# CL-400-5-R4.net
KiCad netlist of a schematic drawn in EAGLE
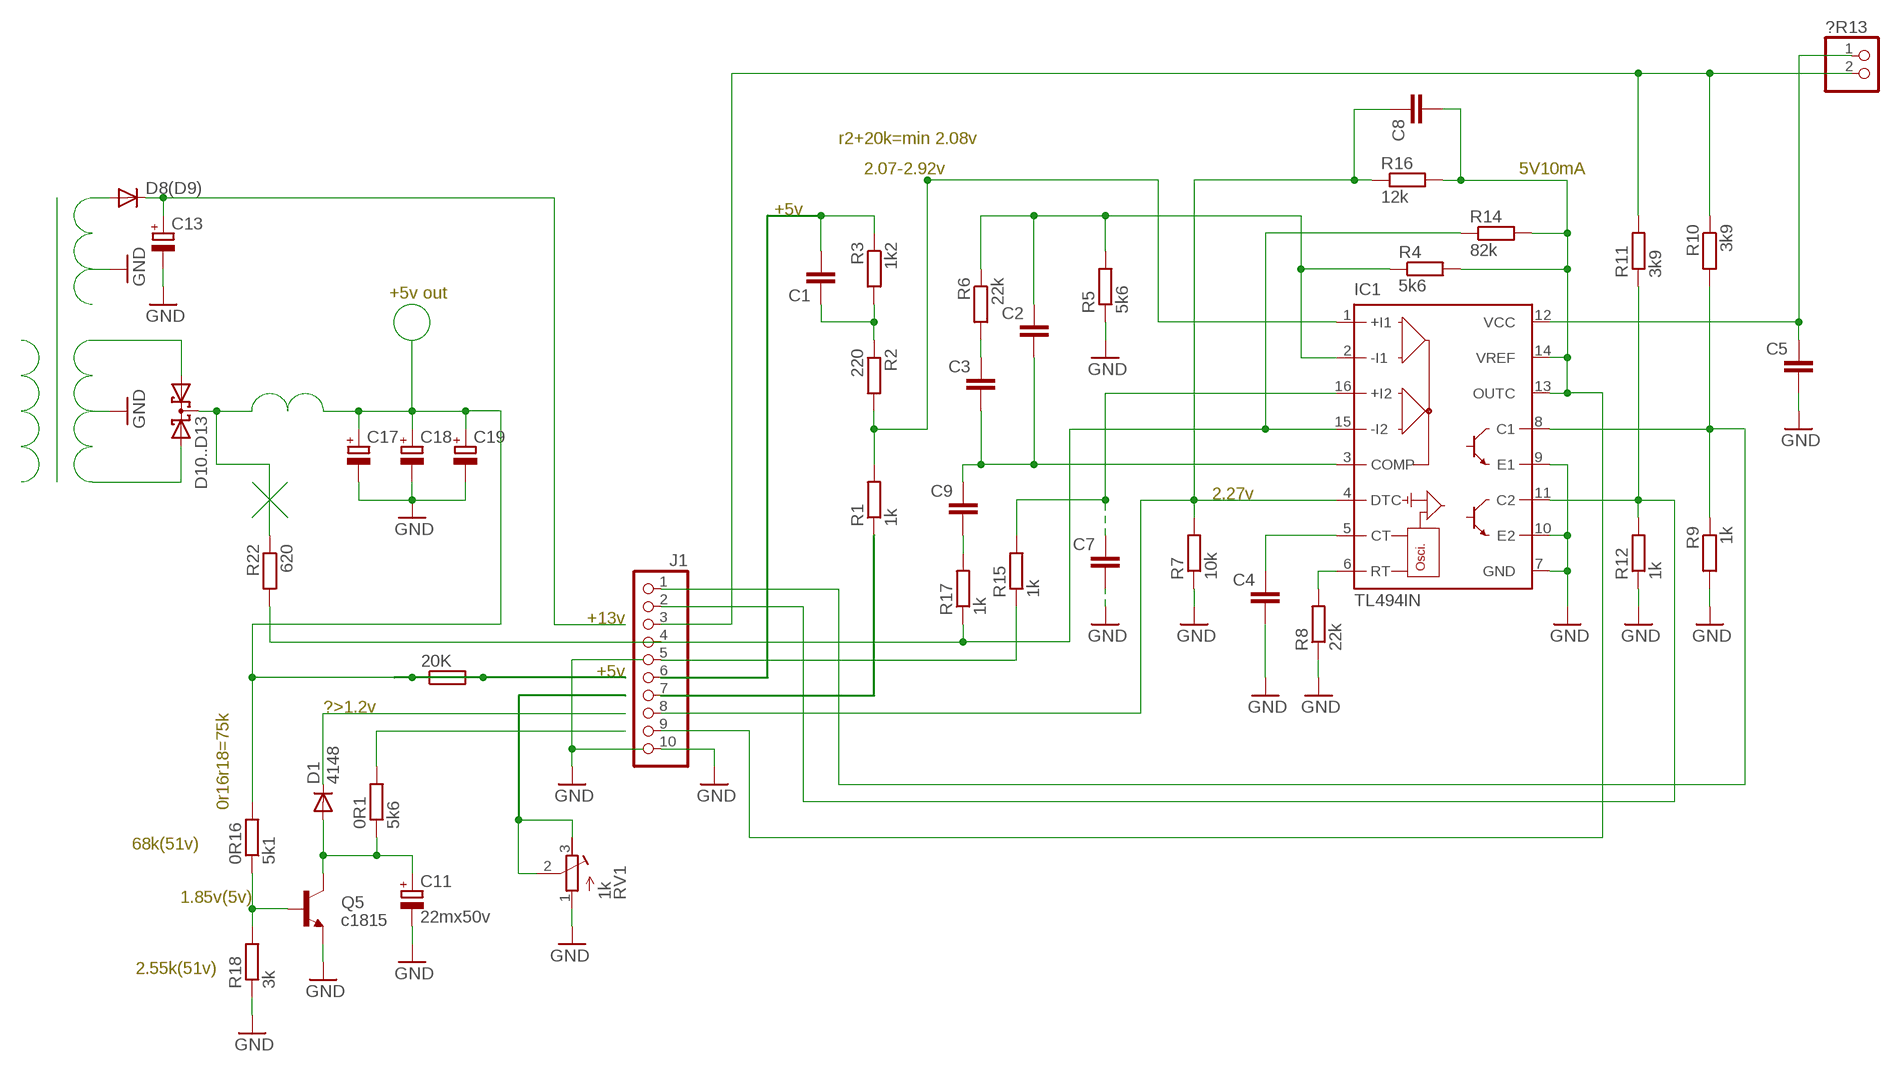
[diagram p0: schematic, sheet 1]

(export (version "E")
  (design (tool "Eeschema 10.0.6"))
  (components
    (comp (ref "0R1")
      (value "5k6")
      (footprint "eagle-import:M0805")
      (libsource (lib "eagle-import") (part "R-EU_M0805"))
    )
    (comp (ref "0R16")
      (value "5k1")
      (footprint "eagle-import:M0805")
      (libsource (lib "eagle-import") (part "R-EU_M0805"))
    )
    (comp (ref "20K")
      (value "R-EU_M0805")
      (footprint "eagle-import:M0805")
      (libsource (lib "eagle-import") (part "R-EU_M0805"))
    )
    (comp (ref "?R13")
      (value "PINHD-1X2")
      (footprint "eagle-import:1X02")
      (libsource (lib "eagle-import") (part "PINHD-1X2"))
    )
    (comp (ref "C1")
      (value "C-EUC0805")
      (footprint "eagle-import:C0805")
      (libsource (lib "eagle-import") (part "C-EUC0805"))
    )
    (comp (ref "C2")
      (value "C-EUC0805")
      (footprint "eagle-import:C0805")
      (libsource (lib "eagle-import") (part "C-EUC0805"))
    )
    (comp (ref "C3")
      (value "C-EUC0805")
      (footprint "eagle-import:C0805")
      (libsource (lib "eagle-import") (part "C-EUC0805"))
    )
    (comp (ref "C4")
      (value "C-EUC0805")
      (footprint "eagle-import:C0805")
      (libsource (lib "eagle-import") (part "C-EUC0805"))
    )
    (comp (ref "C5")
      (value "C-EUC0805")
      (footprint "eagle-import:C0805")
      (libsource (lib "eagle-import") (part "C-EUC0805"))
    )
    (comp (ref "C7")
      (value "C-EUC0805")
      (footprint "eagle-import:C0805")
      (libsource (lib "eagle-import") (part "C-EUC0805"))
    )
    (comp (ref "C8")
      (value "C-EUC0805")
      (footprint "eagle-import:C0805")
      (libsource (lib "eagle-import") (part "C-EUC0805"))
    )
    (comp (ref "C9")
      (value "C-EUC0805")
      (footprint "eagle-import:C0805")
      (libsource (lib "eagle-import") (part "C-EUC0805"))
    )
    (comp (ref "C11")
      (value "22mx50v")
      (footprint "eagle-import:B45181B")
      (libsource (lib "eagle-import") (part "CPOL-EUB45181B"))
    )
    (comp (ref "C13")
      (value "CPOL-EUE7.5-16")
      (footprint "eagle-import:E7,5-16")
      (libsource (lib "eagle-import") (part "CPOL-EUE7.5-16"))
    )
    (comp (ref "C17")
      (value "CPOL-EUE7.5-16")
      (footprint "eagle-import:E7,5-16")
      (libsource (lib "eagle-import") (part "CPOL-EUE7.5-16"))
    )
    (comp (ref "C18")
      (value "CPOL-EUE7.5-16")
      (footprint "eagle-import:E7,5-16")
      (libsource (lib "eagle-import") (part "CPOL-EUE7.5-16"))
    )
    (comp (ref "C19")
      (value "CPOL-EUE7.5-16")
      (footprint "eagle-import:E7,5-16")
      (libsource (lib "eagle-import") (part "CPOL-EUE7.5-16"))
    )
    (comp (ref "D1")
      (value "4148")
      (footprint "eagle-import:DO35-7")
      (libsource (lib "eagle-import") (part "1N4148DO35-7"))
    )
    (comp (ref "D8(D9)")
      (value "1N4148DO35-7")
      (footprint "eagle-import:DO35-7")
      (libsource (lib "eagle-import") (part "1N4148DO35-7"))
    )
    (comp (ref "D10..D13")
      (value "BAS40-05")
      (footprint "eagle-import:SOT23")
      (libsource (lib "eagle-import") (part "BAS40-05"))
    )
    (comp (ref "IC1")
      (value "TL494IN")
      (footprint "eagle-import:SO16")
      (libsource (lib "eagle-import") (part "TL494DB"))
    )
    (comp (ref "J1")
      (value "PINHD-1X10/90")
      (footprint "eagle-import:1X10_90")
      (libsource (lib "eagle-import") (part "PINHD-1X10/90"))
    )
    (comp (ref "Q5")
      (value "c1815")
      (footprint "eagle-import:TO92-ECB")
      (libsource (lib "eagle-import") (part "-NPN-TO92-ECB"))
    )
    (comp (ref "R1")
      (value "1k")
      (footprint "eagle-import:M0805")
      (libsource (lib "eagle-import") (part "R-EU_M0805"))
    )
    (comp (ref "R2")
      (value "220")
      (footprint "eagle-import:M0805")
      (libsource (lib "eagle-import") (part "R-EU_M0805"))
    )
    (comp (ref "R3")
      (value "1k2")
      (footprint "eagle-import:M0805")
      (libsource (lib "eagle-import") (part "R-EU_M0805"))
    )
    (comp (ref "R4")
      (value "5k6")
      (footprint "eagle-import:M0805")
      (libsource (lib "eagle-import") (part "R-EU_M0805"))
    )
    (comp (ref "R5")
      (value "5k6")
      (footprint "eagle-import:M0805")
      (libsource (lib "eagle-import") (part "R-EU_M0805"))
    )
    (comp (ref "R6")
      (value "22k")
      (footprint "eagle-import:M0805")
      (libsource (lib "eagle-import") (part "R-EU_M0805"))
    )
    (comp (ref "R7")
      (value "10k")
      (footprint "eagle-import:M0805")
      (libsource (lib "eagle-import") (part "R-EU_M0805"))
    )
    (comp (ref "R8")
      (value "22k")
      (footprint "eagle-import:M0805")
      (libsource (lib "eagle-import") (part "R-EU_M0805"))
    )
    (comp (ref "R9")
      (value "1k")
      (footprint "eagle-import:M0805")
      (libsource (lib "eagle-import") (part "R-EU_M0805"))
    )
    (comp (ref "R10")
      (value "3k9")
      (footprint "eagle-import:M0805")
      (libsource (lib "eagle-import") (part "R-EU_M0805"))
    )
    (comp (ref "R11")
      (value "3k9")
      (footprint "eagle-import:M0805")
      (libsource (lib "eagle-import") (part "R-EU_M0805"))
    )
    (comp (ref "R12")
      (value "1k")
      (footprint "eagle-import:M0805")
      (libsource (lib "eagle-import") (part "R-EU_M0805"))
    )
    (comp (ref "R14")
      (value "82k")
      (footprint "eagle-import:M0805")
      (libsource (lib "eagle-import") (part "R-EU_M0805"))
    )
    (comp (ref "R15")
      (value "1k")
      (footprint "eagle-import:M0805")
      (libsource (lib "eagle-import") (part "R-EU_M0805"))
    )
    (comp (ref "R16")
      (value "12k")
      (footprint "eagle-import:M0805")
      (libsource (lib "eagle-import") (part "R-EU_M0805"))
    )
    (comp (ref "R17")
      (value "1k")
      (footprint "eagle-import:M0805")
      (libsource (lib "eagle-import") (part "R-EU_M0805"))
    )
    (comp (ref "R18")
      (value "3k")
      (footprint "eagle-import:M0805")
      (libsource (lib "eagle-import") (part "R-EU_M0805"))
    )
    (comp (ref "R22")
      (value "620")
      (footprint "eagle-import:M0805")
      (libsource (lib "eagle-import") (part "R-EU_M0805"))
    )
    (comp (ref "RV1")
      (value "1k")
      (footprint "eagle-import:RTRIM74X")
      (libsource (lib "eagle-import") (part "R-TRIMM74X"))
    )
  )
  (nets
    (net (code "1") (name "GND") (class "Default")
      (node (ref "C11") (pin "-") (pinfunction "-_-") (pintype "passive"))
      (node (ref "C13") (pin "-") (pinfunction "-_-") (pintype "passive"))
      (node (ref "C17") (pin "-") (pinfunction "-_-") (pintype "passive"))
      (node (ref "C18") (pin "-") (pinfunction "-_-") (pintype "passive"))
      (node (ref "C19") (pin "-") (pinfunction "-_-") (pintype "passive"))
      (node (ref "C4") (pin "2") (pinfunction "2_2") (pintype "passive"))
      (node (ref "C5") (pin "2") (pinfunction "2_2") (pintype "passive"))
      (node (ref "C7") (pin "2") (pinfunction "2_2") (pintype "passive"))
      (node (ref "D10..D13") (pin "1") (pinfunction "A1_1") (pintype "passive"))
      (node (ref "D10..D13") (pin "2") (pinfunction "A2_2") (pintype "passive"))
      (node (ref "D8(D9)") (pin "A") (pinfunction "A_A") (pintype "passive"))
      (node (ref "IC1") (pin "10") (pinfunction "E2_10") (pintype "passive"))
      (node (ref "IC1") (pin "7") (pinfunction "GND_7") (pintype "power_in"))
      (node (ref "IC1") (pin "9") (pinfunction "E1_9") (pintype "passive"))
      (node (ref "J1") (pin "10") (pinfunction "10_10") (pintype "passive"))
      (node (ref "Q5") (pin "E") (pinfunction "E_E") (pintype "passive"))
      (node (ref "R12") (pin "1") (pinfunction "1_1") (pintype "passive"))
      (node (ref "R18") (pin "1") (pinfunction "1_1") (pintype "passive"))
      (node (ref "R5") (pin "1") (pinfunction "1_1") (pintype "passive"))
      (node (ref "R7") (pin "1") (pinfunction "1_1") (pintype "passive"))
      (node (ref "R8") (pin "1") (pinfunction "1_1") (pintype "passive"))
      (node (ref "R9") (pin "2") (pinfunction "2_2") (pintype "passive"))
      (node (ref "RV1") (pin "1") (pinfunction "E_1") (pintype "passive"))
    )
    (net (code "2") (name "Net-(0R1-Pad1)") (class "Default")
      (node (ref "0R1") (pin "1") (pinfunction "1_1") (pintype "passive"))
      (node (ref "C11") (pin "+") (pinfunction "+_+") (pintype "passive"))
      (node (ref "D1") (pin "A") (pinfunction "A_A") (pintype "passive"))
      (node (ref "Q5") (pin "C") (pinfunction "C_C") (pintype "passive"))
    )
    (net (code "3") (name "Net-(0R16-Pad1)") (class "Default")
      (node (ref "0R16") (pin "1") (pinfunction "1_1") (pintype "passive"))
      (node (ref "Q5") (pin "B") (pinfunction "B_B") (pintype "passive"))
      (node (ref "R18") (pin "2") (pinfunction "2_2") (pintype "passive"))
    )
    (net (code "4") (name "Net-(?R13-Pad2)") (class "Default")
      (node (ref "?R13") (pin "2") (pinfunction "2_2") (pintype "passive"))
      (node (ref "J1") (pin "3") (pinfunction "3_3") (pintype "passive"))
      (node (ref "R10") (pin "1") (pinfunction "1_1") (pintype "passive"))
      (node (ref "R11") (pin "2") (pinfunction "2_2") (pintype "passive"))
    )
    (net (code "5") (name "Net-(C1-Pad1)") (class "Default")
      (node (ref "C1") (pin "1") (pinfunction "1_1") (pintype "passive"))
      (node (ref "R2") (pin "1") (pinfunction "1_1") (pintype "passive"))
      (node (ref "R3") (pin "2") (pinfunction "2_2") (pintype "passive"))
    )
    (net (code "6") (name "Net-(C1-Pad2)") (class "Default")
      (node (ref "C1") (pin "2") (pinfunction "2_2") (pintype "passive"))
      (node (ref "J1") (pin "6") (pinfunction "6_6") (pintype "passive"))
      (node (ref "R3") (pin "1") (pinfunction "1_1") (pintype "passive"))
    )
    (net (code "7") (name "Net-(C3-Pad1)") (class "Default")
      (node (ref "C3") (pin "1") (pinfunction "1_1") (pintype "passive"))
      (node (ref "R6") (pin "2") (pinfunction "2_2") (pintype "passive"))
    )
    (net (code "8") (name "Net-(C9-Pad2)") (class "Default")
      (node (ref "C9") (pin "2") (pinfunction "2_2") (pintype "passive"))
      (node (ref "R17") (pin "2") (pinfunction "2_2") (pintype "passive"))
    )
    (net (code "9") (name "Net-(C13-Pad+)") (class "Default")
      (node (ref "C13") (pin "+") (pinfunction "+_+") (pintype "passive"))
      (node (ref "D8(D9)") (pin "C") (pinfunction "C_C") (pintype "passive"))
    )
    (net (code "10") (name "Net-(D10..D13-C)") (class "Default")
      (node (ref "0R16") (pin "2") (pinfunction "2_2") (pintype "passive"))
      (node (ref "20K") (pin "1") (pinfunction "1_1") (pintype "passive"))
      (node (ref "20K") (pin "2") (pinfunction "2_2") (pintype "passive"))
      (node (ref "C17") (pin "+") (pinfunction "+_+") (pintype "passive"))
      (node (ref "C18") (pin "+") (pinfunction "+_+") (pintype "passive"))
      (node (ref "C19") (pin "+") (pinfunction "+_+") (pintype "passive"))
      (node (ref "D10..D13") (pin "3") (pinfunction "C_3") (pintype "passive"))
      (node (ref "R22") (pin "1") (pinfunction "1_1") (pintype "passive"))
    )
    (net (code "11") (name "Net-(IC1-+I1)") (class "Default")
      (node (ref "IC1") (pin "1") (pinfunction "+I1_1") (pintype "input"))
      (node (ref "R1") (pin "2") (pinfunction "2_2") (pintype "passive"))
      (node (ref "R2") (pin "2") (pinfunction "2_2") (pintype "passive"))
    )
    (net (code "12") (name "Net-(IC1-+I2)") (class "Default")
      (node (ref "C7") (pin "1") (pinfunction "1_1") (pintype "passive"))
      (node (ref "IC1") (pin "16") (pinfunction "+I2_16") (pintype "input"))
      (node (ref "R15") (pin "2") (pinfunction "2_2") (pintype "passive"))
    )
    (net (code "13") (name "Net-(IC1--I1)") (class "Default")
      (node (ref "C2") (pin "1") (pinfunction "1_1") (pintype "passive"))
      (node (ref "IC1") (pin "2") (pinfunction "-I1_2") (pintype "input"))
      (node (ref "R4") (pin "1") (pinfunction "1_1") (pintype "passive"))
      (node (ref "R5") (pin "2") (pinfunction "2_2") (pintype "passive"))
      (node (ref "R6") (pin "1") (pinfunction "1_1") (pintype "passive"))
    )
    (net (code "14") (name "Net-(IC1--I2)") (class "Default")
      (node (ref "IC1") (pin "15") (pinfunction "-I2_15") (pintype "input"))
      (node (ref "J1") (pin "4") (pinfunction "4_4") (pintype "passive"))
      (node (ref "R14") (pin "1") (pinfunction "1_1") (pintype "passive"))
      (node (ref "R17") (pin "1") (pinfunction "1_1") (pintype "passive"))
      (node (ref "R22") (pin "2") (pinfunction "2_2") (pintype "passive"))
    )
    (net (code "15") (name "Net-(IC1-C1)") (class "Default")
      (node (ref "IC1") (pin "8") (pinfunction "C1_8") (pintype "passive"))
      (node (ref "J1") (pin "1") (pinfunction "1_1") (pintype "passive"))
      (node (ref "R10") (pin "2") (pinfunction "2_2") (pintype "passive"))
      (node (ref "R9") (pin "1") (pinfunction "1_1") (pintype "passive"))
    )
    (net (code "16") (name "Net-(IC1-C2)") (class "Default")
      (node (ref "IC1") (pin "11") (pinfunction "C2_11") (pintype "passive"))
      (node (ref "J1") (pin "2") (pinfunction "2_2") (pintype "passive"))
      (node (ref "R11") (pin "1") (pinfunction "1_1") (pintype "passive"))
      (node (ref "R12") (pin "2") (pinfunction "2_2") (pintype "passive"))
    )
    (net (code "17") (name "Net-(IC1-COMP)") (class "Default")
      (node (ref "C2") (pin "2") (pinfunction "2_2") (pintype "passive"))
      (node (ref "C3") (pin "2") (pinfunction "2_2") (pintype "passive"))
      (node (ref "C9") (pin "1") (pinfunction "1_1") (pintype "passive"))
      (node (ref "IC1") (pin "3") (pinfunction "COMP_3") (pintype "passive"))
    )
    (net (code "18") (name "Net-(IC1-CT)") (class "Default")
      (node (ref "C4") (pin "1") (pinfunction "1_1") (pintype "passive"))
      (node (ref "IC1") (pin "5") (pinfunction "CT_5") (pintype "input"))
    )
    (net (code "19") (name "Net-(IC1-DTC)") (class "Default")
      (node (ref "C8") (pin "1") (pinfunction "1_1") (pintype "passive"))
      (node (ref "IC1") (pin "4") (pinfunction "DTC_4") (pintype "input"))
      (node (ref "J1") (pin "8") (pinfunction "8_8") (pintype "passive"))
      (node (ref "R16") (pin "1") (pinfunction "1_1") (pintype "passive"))
      (node (ref "R7") (pin "2") (pinfunction "2_2") (pintype "passive"))
    )
    (net (code "20") (name "Net-(IC1-OUTC)") (class "Default")
      (node (ref "C8") (pin "2") (pinfunction "2_2") (pintype "passive"))
      (node (ref "IC1") (pin "13") (pinfunction "OUTC_13") (pintype "output"))
      (node (ref "IC1") (pin "14") (pinfunction "VREF_14") (pintype "input"))
      (node (ref "J1") (pin "9") (pinfunction "9_9") (pintype "passive"))
      (node (ref "R14") (pin "2") (pinfunction "2_2") (pintype "passive"))
      (node (ref "R16") (pin "2") (pinfunction "2_2") (pintype "passive"))
      (node (ref "R4") (pin "2") (pinfunction "2_2") (pintype "passive"))
    )
    (net (code "21") (name "Net-(IC1-RT)") (class "Default")
      (node (ref "IC1") (pin "6") (pinfunction "RT_6") (pintype "input"))
      (node (ref "R8") (pin "2") (pinfunction "2_2") (pintype "passive"))
    )
    (net (code "22") (name "Net-(IC1-VCC)") (class "Default")
      (node (ref "?R13") (pin "1") (pinfunction "1_1") (pintype "passive"))
      (node (ref "C5") (pin "1") (pinfunction "1_1") (pintype "passive"))
      (node (ref "IC1") (pin "12") (pinfunction "VCC_12") (pintype "power_in"))
    )
    (net (code "23") (name "Net-(J1-Pad5)") (class "Default")
      (node (ref "J1") (pin "5") (pinfunction "5_5") (pintype "passive"))
      (node (ref "R15") (pin "1") (pinfunction "1_1") (pintype "passive"))
    )
    (net (code "24") (name "Net-(J1-Pad7)") (class "Default")
      (node (ref "J1") (pin "7") (pinfunction "7_7") (pintype "passive"))
      (node (ref "R1") (pin "1") (pinfunction "1_1") (pintype "passive"))
    )
    (net (code "25") (name "Net-(RV1-A)") (class "Default")
      (node (ref "RV1") (pin "2") (pinfunction "S_2") (pintype "passive"))
      (node (ref "RV1") (pin "3") (pinfunction "A_3") (pintype "passive"))
    )
    (net (code "26") (name "unconnected-(0R1-Pad2)") (class "Default")
      (node (ref "0R1") (pin "2") (pinfunction "2_2") (pintype "passive"))
    )
    (net (code "27") (name "unconnected-(D1-PadC)") (class "Default")
      (node (ref "D1") (pin "C") (pinfunction "C_C") (pintype "passive"))
    )
  )
)
